# slider.net
KiCad netlist of a schematic drawn in EAGLE
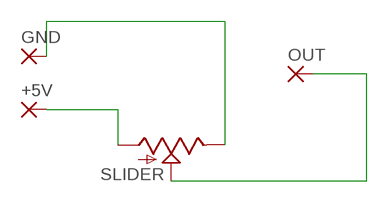
[diagram p0: schematic, sheet 1]

(export (version "E")
  (design (tool "Eeschema 10.0.6"))
  (components
    (comp (ref "+5V")
      (value "2,54/1,1")
      (footprint "eagle-import:2,54_1,1")
      (libsource (lib "eagle-import") (part "2,54/1,1"))
    )
    (comp (ref "GND")
      (value "2,54/1,1")
      (footprint "eagle-import:2,54_1,1")
      (libsource (lib "eagle-import") (part "2,54/1,1"))
    )
    (comp (ref "OUT")
      (value "2,54/1,1")
      (footprint "eagle-import:2,54_1,1")
      (libsource (lib "eagle-import") (part "2,54/1,1"))
    )
    (comp (ref "SLIDER")
      (value "SLIDER20MM")
      (footprint "eagle-import:SLIDER-SMALL")
      (libsource (lib "eagle-import") (part "SLIDER20MM"))
    )
  )
  (nets
    (net (code "1") (name "Net-(+5V-P)") (class "Default")
      (node (ref "+5V") (pin "1") (pinfunction "P_1") (pintype "passive"))
      (node (ref "SLIDER") (pin "BOTTOM") (pinfunction "A_BOTTOM") (pintype "passive"))
    )
    (net (code "2") (name "Net-(GND-P)") (class "Default")
      (node (ref "GND") (pin "1") (pinfunction "P_1") (pintype "passive"))
      (node (ref "SLIDER") (pin "TOP") (pinfunction "E_TOP") (pintype "passive"))
    )
    (net (code "3") (name "Net-(OUT-P)") (class "Default")
      (node (ref "OUT") (pin "1") (pinfunction "P_1") (pintype "passive"))
      (node (ref "SLIDER") (pin "WIPER") (pinfunction "S_WIPER") (pintype "passive"))
    )
  )
)
